# Power_distribution.net
KiCad netlist of a schematic drawn in Altium Designer
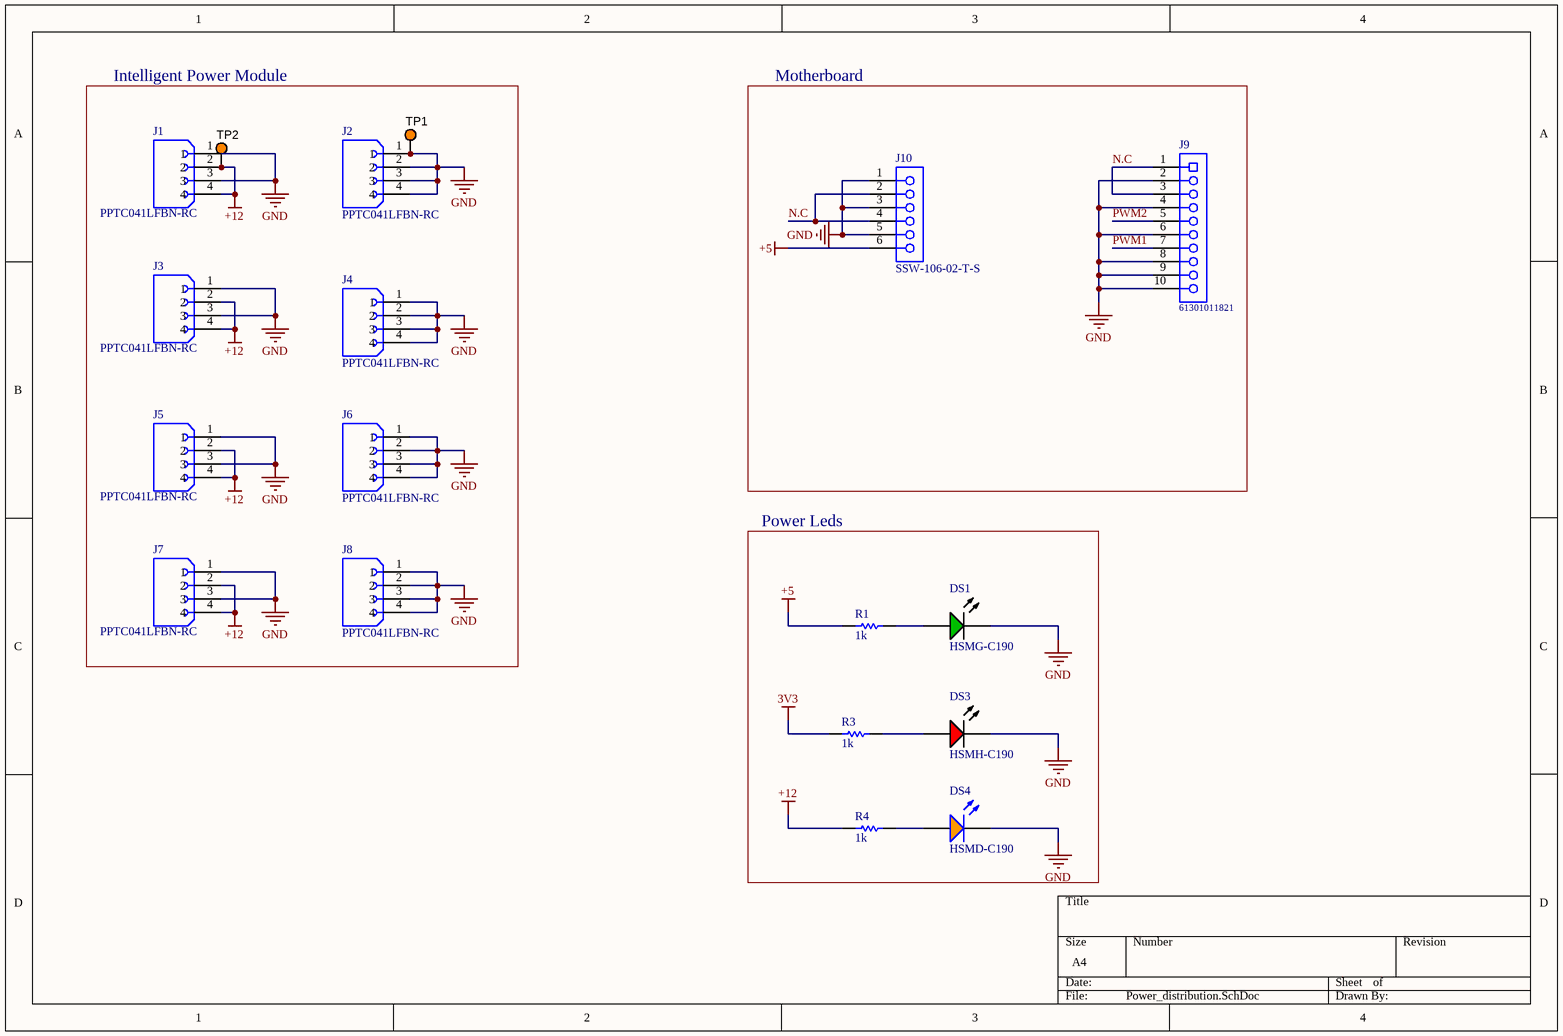
[diagram p0: Power_distribution.SchDoc]

(export (version "E")
  (design (tool "Eeschema 10.0.6"))
  (components
    (comp (ref "DS1")
      (value "HSMG-C190")
      (footprint "AVAG-HSMX-C190_V")
      (description "Chip LED, Green, 2.2 V, -40 to 85 degC, 2-Pin SMD, RoHS, Tape and Reel")
      (libsource (lib "Altium Content Vault") (part "LED-GREEN-AK-2"))
    )
    (comp (ref "DS3")
      (value "HSMH-C190")
      (footprint "AVAG-HSMX-C190_V")
      (description "LED Uni-Color Red, 65 mW, 20 mA, -40 to 85 degC, 2-Pin SMD, RoHS, Tape and Reel")
      (libsource (lib "Altium Content Vault") (part "LED-RED-AK-2"))
    )
    (comp (ref "DS4")
      (value "HSMD-C190")
      (footprint "AVAG-HSMX-C190_V")
      (description "LED Uni-Color Orange, 52 mW, 20 mA, -40 to 85 degC, 2-Pin SMD, RoHS, Tape and Reel")
      (libsource (lib "Altium Content Vault") (part "LED-ORANGE-AK-2"))
    )
    (comp (ref "J1")
      (value "PPTC041LFBN-RC")
      (footprint "SULLINS_PPTC041LFBN-RC")
      (description "4 Position Header Connector Through Hole")
      (fields (field (name "MF") "Sullins Connector"))
      (libsource (lib "PPTC041LFBN-RC") (part "PPTC041LFBN-RC"))
    )
    (comp (ref "J2")
      (value "PPTC041LFBN-RC")
      (footprint "SULLINS_PPTC041LFBN-RC")
      (description "4 Position Header Connector Through Hole")
      (fields (field (name "MF") "Sullins Connector"))
      (libsource (lib "PPTC041LFBN-RC") (part "PPTC041LFBN-RC"))
    )
    (comp (ref "J3")
      (value "PPTC041LFBN-RC")
      (footprint "SULLINS_PPTC041LFBN-RC")
      (description "4 Position Header Connector Through Hole")
      (fields (field (name "MF") "Sullins Connector"))
      (libsource (lib "PPTC041LFBN-RC") (part "PPTC041LFBN-RC"))
    )
    (comp (ref "J4")
      (value "PPTC041LFBN-RC")
      (footprint "SULLINS_PPTC041LFBN-RC")
      (description "4 Position Header Connector Through Hole")
      (fields (field (name "MF") "Sullins Connector"))
      (libsource (lib "PPTC041LFBN-RC") (part "PPTC041LFBN-RC"))
    )
    (comp (ref "J5")
      (value "PPTC041LFBN-RC")
      (footprint "SULLINS_PPTC041LFBN-RC")
      (description "4 Position Header Connector Through Hole")
      (fields (field (name "MF") "Sullins Connector"))
      (libsource (lib "PPTC041LFBN-RC") (part "PPTC041LFBN-RC"))
    )
    (comp (ref "J6")
      (value "PPTC041LFBN-RC")
      (footprint "SULLINS_PPTC041LFBN-RC")
      (description "4 Position Header Connector Through Hole")
      (fields (field (name "MF") "Sullins Connector"))
      (libsource (lib "PPTC041LFBN-RC") (part "PPTC041LFBN-RC"))
    )
    (comp (ref "J7")
      (value "PPTC041LFBN-RC")
      (footprint "SULLINS_PPTC041LFBN-RC")
      (description "4 Position Header Connector Through Hole")
      (fields (field (name "MF") "Sullins Connector"))
      (libsource (lib "PPTC041LFBN-RC") (part "PPTC041LFBN-RC"))
    )
    (comp (ref "J8")
      (value "PPTC041LFBN-RC")
      (footprint "SULLINS_PPTC041LFBN-RC")
      (description "4 Position Header Connector Through Hole")
      (fields (field (name "MF") "Sullins Connector"))
      (libsource (lib "PPTC041LFBN-RC") (part "PPTC041LFBN-RC"))
    )
    (comp (ref "J9")
      (value "61301011821")
      (footprint "61301011821")
      (description "THT Vertical Socket Header WR-PHD, Pitch 2.54 mm, Single Row, 10 pins")
      (fields (field (name "MANUFACTURER") "Wurth Elektronik") (field (name "PUBLISHER") "WurthElektronik"))
      (libsource (lib "Altium Content Vault") (part "WE-CN-1P-F-R10"))
    )
    (comp (ref "J10")
      (value "SSW-106-02-T-S")
      (footprint "SMTC-SSW-106-02-X-S")
      (description "SQ Post Socket, Through-hole, Vertical, -55 to 105 degC, 2.54mm Pitch, 6-Pin, Female, RoHS")
      (fields (field (name "MANUFACTURER") "Samtec"))
      (libsource (lib "Altium Content Vault") (part "SMTC-SSW-106-02-X-S-X"))
    )
    (comp (ref "R1")
      (value "1k")
      (footprint "RESC1609X50X30NL8T20")
      (description "Chip Resistor, 0 Ohm, Jumper, 100 mW, -55 to 155 degC, 0603 (1608 Metric), RoHS, Tape and Reel")
      (fields (field (name "MANUFACTURER") "Vishay Semiconductor"))
      (libsource (lib "Altium Content Vault") (part "RES-2"))
    )
    (comp (ref "R3")
      (value "1k")
      (footprint "RESC1609X50X30NL8T20")
      (description "Chip Resistor, 0 Ohm, Jumper, 100 mW, -55 to 155 degC, 0603 (1608 Metric), RoHS, Tape and Reel")
      (fields (field (name "MANUFACTURER") "Vishay Semiconductor"))
      (libsource (lib "Altium Content Vault") (part "RES-2"))
    )
    (comp (ref "R4")
      (value "1k")
      (footprint "RESC1609X50X30NL8T20")
      (description "Chip Resistor, 0 Ohm, Jumper, 100 mW, -55 to 155 degC, 0603 (1608 Metric), RoHS, Tape and Reel")
      (fields (field (name "MANUFACTURER") "Vishay Semiconductor"))
      (libsource (lib "Altium Content Vault") (part "RES-2"))
    )
    (comp (ref "TP1")
      (value "5003")
      (footprint "KSTN-5003")
      (description "Test Point, Orange, 1-Pin THD, RoHS")
      (libsource (lib "Altium Content Vault") (part "TESTPOINT_ORANGE"))
    )
    (comp (ref "TP2")
      (value "5003")
      (footprint "KSTN-5003")
      (description "Test Point, Orange, 1-Pin THD, RoHS")
      (libsource (lib "Altium Content Vault") (part "TESTPOINT_ORANGE"))
    )
  )
  (nets
    (net (code "1") (name "+5") (class "Default")
      (node (ref "J10") (pin "6") (pinfunction "6_6") (pintype "passive"))
      (node (ref "R1") (pin "1") (pinfunction "1_1") (pintype "passive"))
    )
    (net (code "2") (name "+12") (class "Default")
      (node (ref "J1") (pin "2") (pinfunction "2_2") (pintype "passive"))
      (node (ref "J1") (pin "4") (pinfunction "4_4") (pintype "passive"))
      (node (ref "J3") (pin "2") (pinfunction "2_2") (pintype "passive"))
      (node (ref "J3") (pin "4") (pinfunction "4_4") (pintype "passive"))
      (node (ref "J5") (pin "2") (pinfunction "2_2") (pintype "passive"))
      (node (ref "J5") (pin "4") (pinfunction "4_4") (pintype "passive"))
      (node (ref "J7") (pin "2") (pinfunction "2_2") (pintype "passive"))
      (node (ref "J7") (pin "4") (pinfunction "4_4") (pintype "passive"))
      (node (ref "R4") (pin "1") (pinfunction "1_1") (pintype "passive"))
      (node (ref "TP2") (pin "1") (pinfunction "1_1") (pintype "passive"))
    )
    (net (code "3") (name "/N.C") (class "Default")
      (node (ref "J10") (pin "2") (pinfunction "2_2") (pintype "passive"))
      (node (ref "J10") (pin "4") (pinfunction "4_4") (pintype "passive"))
      (node (ref "J9") (pin "1") (pinfunction "1_1") (pintype "passive"))
      (node (ref "J9") (pin "3") (pinfunction "3_3") (pintype "passive"))
    )
    (net (code "4") (name "/PWM1") (class "Default")
      (node (ref "J9") (pin "7") (pinfunction "7_7") (pintype "passive"))
    )
    (net (code "5") (name "/PWM2") (class "Default")
      (node (ref "J9") (pin "5") (pinfunction "5_5") (pintype "passive"))
    )
    (net (code "6") (name "3V3") (class "Default")
      (node (ref "R3") (pin "1") (pinfunction "1_1") (pintype "passive"))
    )
    (net (code "7") (name "GND") (class "Default")
      (node (ref "DS1") (pin "2") (pinfunction "K_2") (pintype "passive"))
      (node (ref "DS3") (pin "2") (pinfunction "K_2") (pintype "passive"))
      (node (ref "DS4") (pin "2") (pinfunction "K_2") (pintype "passive"))
      (node (ref "J1") (pin "1") (pinfunction "1_1") (pintype "passive"))
      (node (ref "J1") (pin "3") (pinfunction "3_3") (pintype "passive"))
      (node (ref "J10") (pin "1") (pinfunction "1_1") (pintype "passive"))
      (node (ref "J10") (pin "3") (pinfunction "3_3") (pintype "passive"))
      (node (ref "J10") (pin "5") (pinfunction "5_5") (pintype "passive"))
      (node (ref "J2") (pin "1") (pinfunction "1_1") (pintype "passive"))
      (node (ref "J2") (pin "2") (pinfunction "2_2") (pintype "passive"))
      (node (ref "J2") (pin "3") (pinfunction "3_3") (pintype "passive"))
      (node (ref "J2") (pin "4") (pinfunction "4_4") (pintype "passive"))
      (node (ref "J3") (pin "1") (pinfunction "1_1") (pintype "passive"))
      (node (ref "J3") (pin "3") (pinfunction "3_3") (pintype "passive"))
      (node (ref "J4") (pin "1") (pinfunction "1_1") (pintype "passive"))
      (node (ref "J4") (pin "2") (pinfunction "2_2") (pintype "passive"))
      (node (ref "J4") (pin "3") (pinfunction "3_3") (pintype "passive"))
      (node (ref "J4") (pin "4") (pinfunction "4_4") (pintype "passive"))
      (node (ref "J5") (pin "1") (pinfunction "1_1") (pintype "passive"))
      (node (ref "J5") (pin "3") (pinfunction "3_3") (pintype "passive"))
      (node (ref "J6") (pin "1") (pinfunction "1_1") (pintype "passive"))
      (node (ref "J6") (pin "2") (pinfunction "2_2") (pintype "passive"))
      (node (ref "J6") (pin "3") (pinfunction "3_3") (pintype "passive"))
      (node (ref "J6") (pin "4") (pinfunction "4_4") (pintype "passive"))
      (node (ref "J7") (pin "1") (pinfunction "1_1") (pintype "passive"))
      (node (ref "J7") (pin "3") (pinfunction "3_3") (pintype "passive"))
      (node (ref "J8") (pin "1") (pinfunction "1_1") (pintype "passive"))
      (node (ref "J8") (pin "2") (pinfunction "2_2") (pintype "passive"))
      (node (ref "J8") (pin "3") (pinfunction "3_3") (pintype "passive"))
      (node (ref "J8") (pin "4") (pinfunction "4_4") (pintype "passive"))
      (node (ref "J9") (pin "10") (pinfunction "10_10") (pintype "passive"))
      (node (ref "J9") (pin "2") (pinfunction "2_2") (pintype "passive"))
      (node (ref "J9") (pin "4") (pinfunction "4_4") (pintype "passive"))
      (node (ref "J9") (pin "6") (pinfunction "6_6") (pintype "passive"))
      (node (ref "J9") (pin "8") (pinfunction "8_8") (pintype "passive"))
      (node (ref "J9") (pin "9") (pinfunction "9_9") (pintype "passive"))
      (node (ref "TP1") (pin "1") (pinfunction "1_1") (pintype "passive"))
    )
    (net (code "8") (name "Net-(DS1-A)") (class "Default")
      (node (ref "DS1") (pin "1") (pinfunction "A_1") (pintype "passive"))
      (node (ref "R1") (pin "2") (pinfunction "2_2") (pintype "passive"))
    )
    (net (code "9") (name "Net-(DS3-A)") (class "Default")
      (node (ref "DS3") (pin "1") (pinfunction "A_1") (pintype "passive"))
      (node (ref "R3") (pin "2") (pinfunction "2_2") (pintype "passive"))
    )
    (net (code "10") (name "Net-(DS4-A)") (class "Default")
      (node (ref "DS4") (pin "1") (pinfunction "A_1") (pintype "passive"))
      (node (ref "R4") (pin "2") (pinfunction "2_2") (pintype "passive"))
    )
  )
)
